# LMAT_AMT_V3.net
KiCad netlist of a schematic drawn in Altium Designer
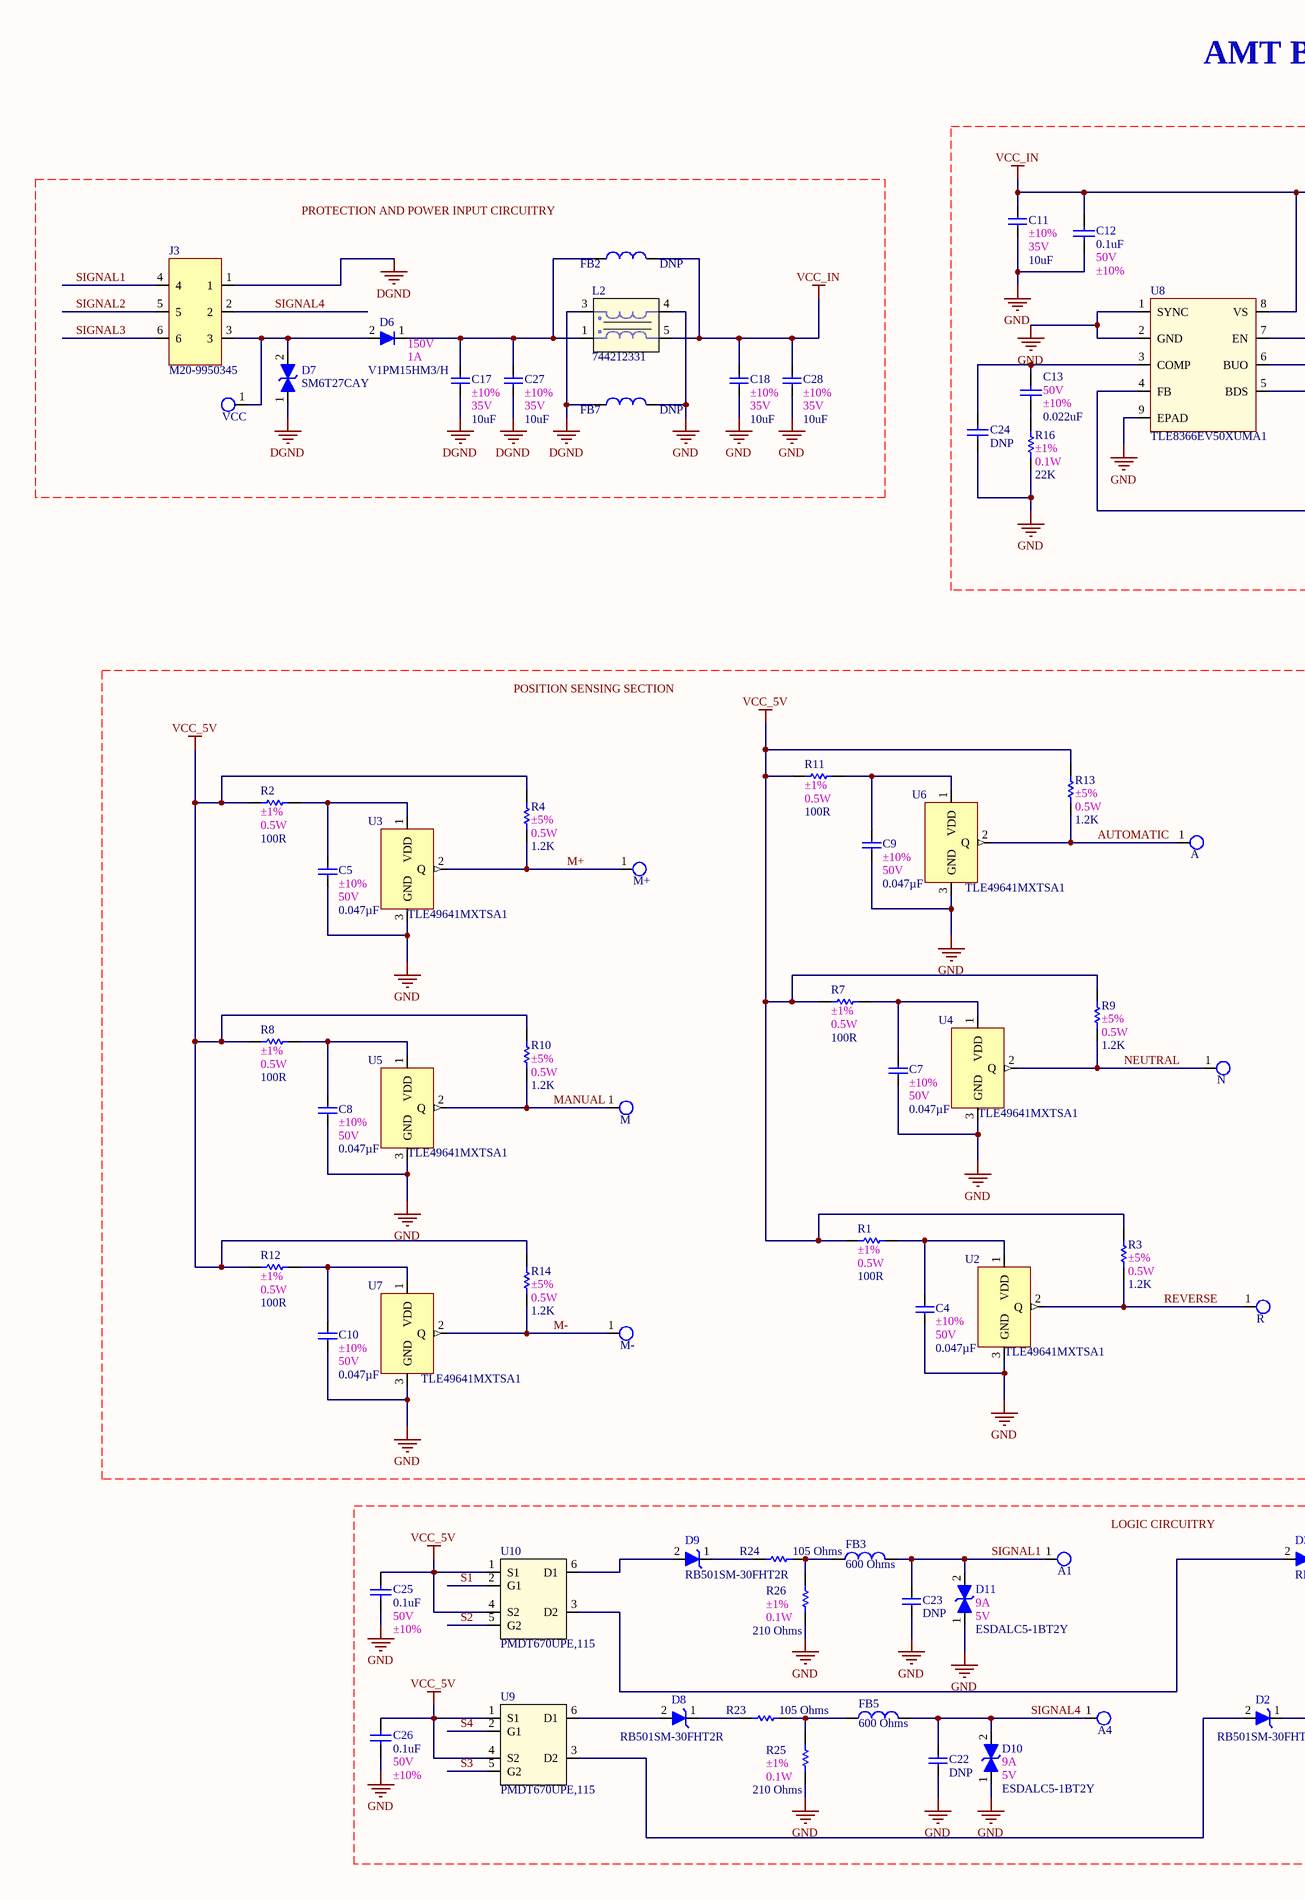
[diagram p0: LMAT_AMT_V3.SchDoc, left]
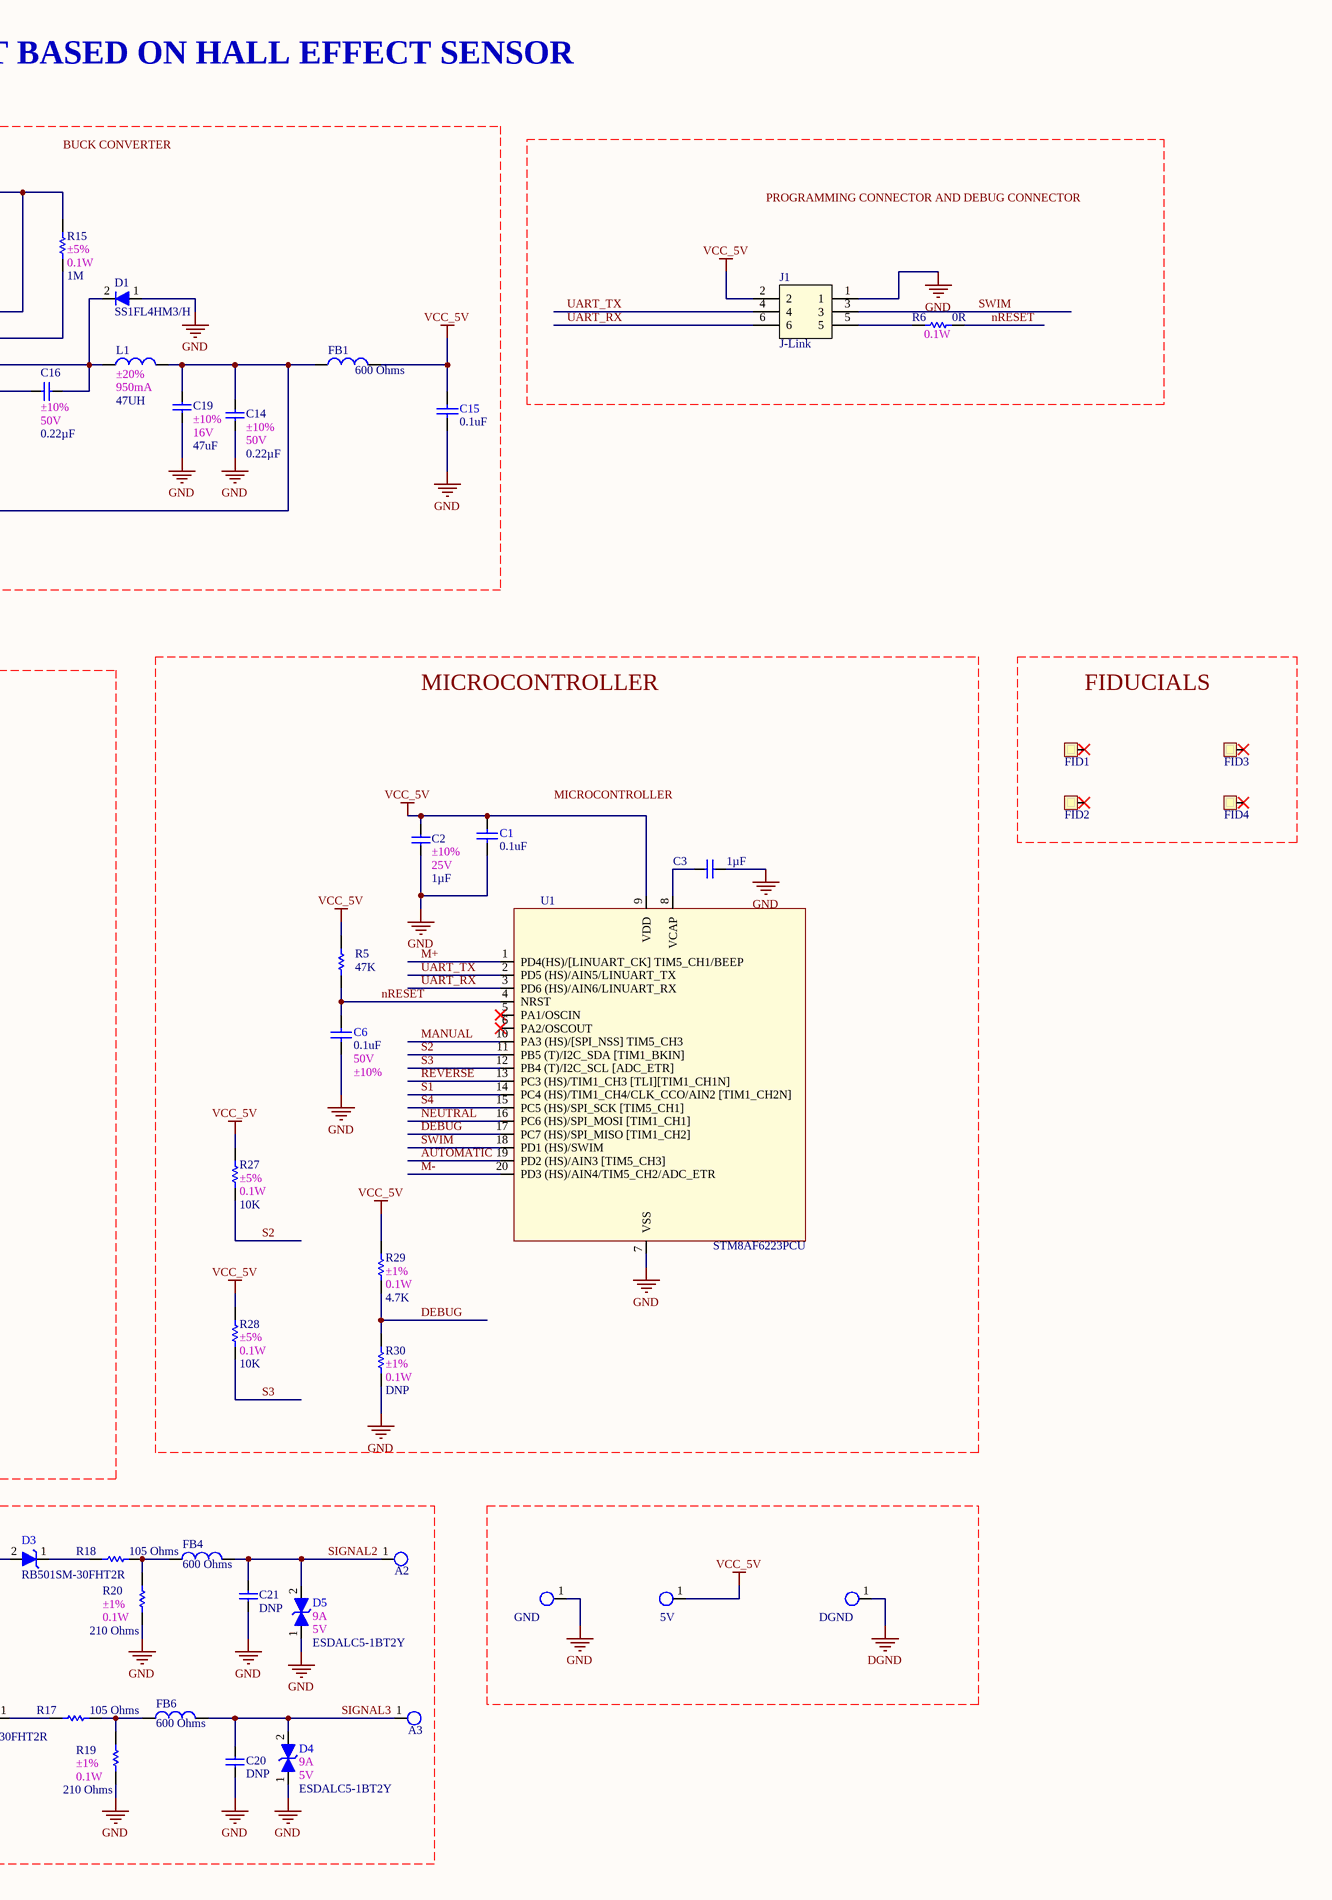
[diagram p1: LMAT_AMT_V3.SchDoc, right]

(export (version "E")
  (design (tool "Eeschema 10.0.6"))
  (components
    (comp (ref "5V")
      (value "Test Point- 35mil")
      (footprint "Master_Library:TP_35M_DIA")
      (fields (field (name "INTERNAL PART NUMBER") "EMS-TP35MIL-S"))
      (libsource (lib "Integrated_Master_Library") (part "EMS-TP35MIL-S"))
    )
    (comp (ref "A")
      (value "Test Point- 35mil")
      (footprint "Master_Library:TP_35M_DIA")
      (fields (field (name "INTERNAL PART NUMBER") "EMS-TP35MIL-S"))
      (libsource (lib "Integrated_Master_Library") (part "EMS-TP35MIL-S"))
    )
    (comp (ref "A1")
      (value "Test Point- 35mil")
      (footprint "Master_Library:TP_35M_DIA")
      (fields (field (name "INTERNAL PART NUMBER") "EMS-TP35MIL-S"))
      (libsource (lib "Integrated_Master_Library") (part "EMS-TP35MIL-S"))
    )
    (comp (ref "A2")
      (value "Test Point- 35mil")
      (footprint "Master_Library:TP_35M_DIA")
      (fields (field (name "INTERNAL PART NUMBER") "EMS-TP35MIL-S"))
      (libsource (lib "Integrated_Master_Library") (part "EMS-TP35MIL-S"))
    )
    (comp (ref "A3")
      (value "Test Point- 35mil")
      (footprint "Master_Library:TP_35M_DIA")
      (fields (field (name "INTERNAL PART NUMBER") "EMS-TP35MIL-S"))
      (libsource (lib "Integrated_Master_Library") (part "EMS-TP35MIL-S"))
    )
    (comp (ref "A4")
      (value "Test Point- 35mil")
      (footprint "Master_Library:TP_35M_DIA")
      (fields (field (name "INTERNAL PART NUMBER") "EMS-TP35MIL-S"))
      (libsource (lib "Integrated_Master_Library") (part "EMS-TP35MIL-S"))
    )
    (comp (ref "C1")
      (value "0.1uF")
      (footprint "Masterlib_auto:SMDC0603")
      (description "CAP CER 0.1UF 50V 10% X7R 0603")
      (fields
        (field (name "MANUFACTURER PART NUMBER") "CGA3E2X7R1H104K080AA")
        (field (name "MANUFACTURER") "TDK Corporation")
      )
      (libsource (lib "Integrated_Master_Library") (part "ECA0U10K50V0-SC"))
    )
    (comp (ref "C2")
      (value "1µF")
      (footprint "Masterlib_auto:SMDC0603")
      (description "CAP CER 1UF 25V X7R 0603")
      (fields
        (field (name "MANUFACTURER") "TDK Corporation")
        (field (name "VENDOR PART NUMBER") "445-173628-1-ND")
        (field (name "2ND AUXILIARY FIELD") "±10%")
        (field (name "1ST AUXILIARY FIELD") "25V")
      )
      (libsource (lib "Integrated_Master_Library (3)") (part "ECA1U00L25V0-SC"))
    )
    (comp (ref "C3")
      (value "1µF")
      (footprint "Masterlib_auto:SMDC0603")
      (description "CAP CER 1UF 25V X7R 0603")
      (fields
        (field (name "MANUFACTURER") "TDK Corporation")
        (field (name "VENDOR PART NUMBER") "445-173628-1-ND")
      )
      (libsource (lib "Integrated_Master_Library (3)") (part "ECA1U00L25V0-SC"))
    )
    (comp (ref "C4")
      (value "0.047µF")
      (footprint "Masterlib_auto:SMDC0603")
      (description "CAP CER 0.047UF 50V X7R 0603")
      (fields
        (field (name "MANUFACTURER") "TDK Corporation")
        (field (name "VENDOR PART NUMBER") "445-5664-1-ND")
        (field (name "2ND AUXILIARY FIELD") "±10%")
        (field (name "1ST AUXILIARY FIELD") "50V")
      )
      (libsource (lib "Integrated_Master_Library") (part "ECA47N0L50V-SC"))
    )
    (comp (ref "C5")
      (value "0.047µF")
      (footprint "Masterlib_auto:SMDC0603")
      (description "CAP CER 0.047UF 50V X7R 0603")
      (fields
        (field (name "MANUFACTURER") "TDK Corporation")
        (field (name "VENDOR PART NUMBER") "445-5664-1-ND")
        (field (name "2ND AUXILIARY FIELD") "±10%")
        (field (name "1ST AUXILIARY FIELD") "50V")
      )
      (libsource (lib "Integrated_Master_Library") (part "ECA47N0L50V-SC"))
    )
    (comp (ref "C6")
      (value "0.1uF")
      (footprint "Masterlib_auto:SMDC0603")
      (description "CAP CER 0.1UF 50V 10% X7R 0603")
      (fields
        (field (name "MANUFACTURER PART NUMBER") "CGA3E2X7R1H104K080AA")
        (field (name "MANUFACTURER") "TDK Corporation")
        (field (name "1ST AUXILIARY FIELD") "50V")
        (field (name "2ND AUXILIARY FIELD") "±10%")
      )
      (libsource (lib "Integrated_Master_Library") (part "ECA0U10K50V0-SC"))
    )
    (comp (ref "C7")
      (value "0.047µF")
      (footprint "Masterlib_auto:SMDC0603")
      (description "CAP CER 0.047UF 50V X7R 0603")
      (fields
        (field (name "MANUFACTURER") "TDK Corporation")
        (field (name "VENDOR PART NUMBER") "445-5664-1-ND")
        (field (name "2ND AUXILIARY FIELD") "±10%")
        (field (name "1ST AUXILIARY FIELD") "50V")
      )
      (libsource (lib "Integrated_Master_Library") (part "ECA47N0L50V-SC"))
    )
    (comp (ref "C8")
      (value "0.047µF")
      (footprint "Masterlib_auto:SMDC0603")
      (description "CAP CER 0.047UF 50V X7R 0603")
      (fields
        (field (name "MANUFACTURER") "TDK Corporation")
        (field (name "VENDOR PART NUMBER") "445-5664-1-ND")
        (field (name "2ND AUXILIARY FIELD") "±10%")
        (field (name "1ST AUXILIARY FIELD") "50V")
      )
      (libsource (lib "Integrated_Master_Library") (part "ECA47N0L50V-SC"))
    )
    (comp (ref "C9")
      (value "0.047µF")
      (footprint "Masterlib_auto:SMDC0603")
      (description "CAP CER 0.047UF 50V X7R 0603")
      (fields
        (field (name "MANUFACTURER") "TDK Corporation")
        (field (name "VENDOR PART NUMBER") "445-5664-1-ND")
        (field (name "2ND AUXILIARY FIELD") "±10%")
        (field (name "1ST AUXILIARY FIELD") "50V")
      )
      (libsource (lib "Integrated_Master_Library") (part "ECA47N0L50V-SC"))
    )
    (comp (ref "C10")
      (value "0.047µF")
      (footprint "Masterlib_auto:SMDC0603")
      (description "CAP CER 0.047UF 50V X7R 0603")
      (fields
        (field (name "MANUFACTURER") "TDK Corporation")
        (field (name "VENDOR PART NUMBER") "445-5664-1-ND")
        (field (name "2ND AUXILIARY FIELD") "±10%")
        (field (name "1ST AUXILIARY FIELD") "50V")
      )
      (libsource (lib "Integrated_Master_Library") (part "ECA47N0L50V-SC"))
    )
    (comp (ref "C11")
      (value "10uF")
      (footprint "Master_Library:SMDC1206")
      (description "CAP CER 10UF 35V X7R 1206")
      (fields
        (field (name "MANUFACTURER") "TDK Corporation")
        (field (name "VENDOR PART NUMBER") "445-174428-1-ND")
        (field (name "2ND AUXILIARY FIELD") "±10%")
        (field (name "1ST AUXILIARY FIELD") "35V")
      )
      (libsource (lib "Master_ Library") (part "ECA10U0L35V0-SG"))
    )
    (comp (ref "C12")
      (value "0.1uF")
      (footprint "Masterlib_auto:SMDC0603")
      (description "CAP CER 0.1UF 50V 10% X7R 0603")
      (fields
        (field (name "MANUFACTURER PART NUMBER") "CGA3E2X7R1H104K080AA")
        (field (name "MANUFACTURER") "TDK Corporation")
        (field (name "1ST AUXILIARY FIELD") "50V")
        (field (name "2ND AUXILIARY FIELD") "±10%")
      )
      (libsource (lib "Integrated_Master_Library") (part "ECA0U10K50V0-SC"))
    )
    (comp (ref "C13")
      (value "0.022uF")
      (footprint "Masterlib_auto:SMDC0603")
      (description "CAP CER 0.022UF 50V 10% X7R 0603")
      (fields
        (field (name "MANUFACTURER PART NUMBER") "CGA3E2X7R1H223K080AA")
        (field (name "MANUFACTURER") "TDK Corporation")
        (field (name "1ST AUXILIARY FIELD") "50V")
        (field (name "2ND AUXILIARY FIELD") "±10%")
      )
      (libsource (lib "Integrated_Master_Library") (part "ECA0U022K50V0-SC"))
    )
    (comp (ref "C14")
      (value "0.22µF")
      (footprint "Masterlib_auto:SMDC0603")
      (description "CAP CER 0.22UF 50V X7R 0603")
      (fields
        (field (name "MANUFACTURER") "Murata Electronics North America")
        (field (name "VENDOR PART NUMBER") "490-14410-1-ND")
        (field (name "2ND AUXILIARY FIELD") "±10%")
        (field (name "1ST AUXILIARY FIELD") "50V")
      )
      (libsource (lib "Integrated_Master_Library (3)") (part "ECA0U22L50V0-SC"))
    )
    (comp (ref "C15")
      (value "0.1uF")
      (footprint "Masterlib_auto:SMDC0603")
      (description "CAP CER 0.1UF 50V 10% X7R 0603")
      (fields
        (field (name "MANUFACTURER PART NUMBER") "CGA3E2X7R1H104K080AA")
        (field (name "MANUFACTURER") "TDK Corporation")
      )
      (libsource (lib "Integrated_Master_Library") (part "ECA0U10K50V0-SC"))
    )
    (comp (ref "C16")
      (value "0.22µF")
      (footprint "Masterlib_auto:SMDC0603")
      (description "CAP CER 0.22UF 50V X7R 0603")
      (fields
        (field (name "MANUFACTURER") "Murata Electronics North America")
        (field (name "VENDOR PART NUMBER") "490-14410-1-ND")
        (field (name "2ND AUXILIARY FIELD") "±10%")
        (field (name "1ST AUXILIARY FIELD") "50V")
      )
      (libsource (lib "Integrated_Master_Library") (part "ECA0U22L50V0-SC"))
    )
    (comp (ref "C17")
      (value "10uF")
      (footprint "Master_Library:SMDC1206")
      (description "CAP CER 10UF 35V X7R 1206")
      (fields
        (field (name "MANUFACTURER") "TDK Corporation")
        (field (name "VENDOR PART NUMBER") "445-174428-1-ND")
        (field (name "2ND AUXILIARY FIELD") "±10%")
        (field (name "1ST AUXILIARY FIELD") "35V")
      )
      (libsource (lib "Master_ Library") (part "ECA10U0L35V0-SG"))
    )
    (comp (ref "C18")
      (value "10uF")
      (footprint "Master_Library:SMDC1206")
      (description "CAP CER 10UF 35V X7R 1206")
      (fields
        (field (name "MANUFACTURER") "TDK Corporation")
        (field (name "VENDOR PART NUMBER") "445-174428-1-ND")
        (field (name "2ND AUXILIARY FIELD") "±10%")
        (field (name "1ST AUXILIARY FIELD") "35V")
      )
      (libsource (lib "Master_ Library") (part "ECA10U0L35V0-SG"))
    )
    (comp (ref "C19")
      (value "47uF")
      (footprint "Master_Library:SMDC1210")
      (description "CAP CER 47UF 16V X6S 1210")
      (fields
        (field (name "MANUFACTURER") "Murata Electronics North America")
        (field (name "VENDOR PART NUMBER") "490-12494-1-ND")
        (field (name "2ND AUXILIARY FIELD") "±10%")
        (field (name "1ST AUXILIARY FIELD") "16V")
      )
      (libsource (lib "Automobile-ML") (part "ECA47U0L16V0-SH"))
    )
    (comp (ref "C20")
      (value "DNP")
      (footprint "Masterlib_auto:SMDC0603")
      (description "CAP CER 10000PF 50V X8R 0603")
      (fields
        (field (name "MANUFACTURER") "TDK Corporation")
        (field (name "VENDOR PART NUMBER") "445-5892-1-ND")
      )
      (libsource (lib "Automobile-ML") (part "ECA0U01L50V0-SC"))
    )
    (comp (ref "C21")
      (value "DNP")
      (footprint "Masterlib_auto:SMDC0603")
      (description "CAP CER 10000PF 50V X8R 0603")
      (fields
        (field (name "MANUFACTURER") "TDK Corporation")
        (field (name "VENDOR PART NUMBER") "445-5892-1-ND")
      )
      (libsource (lib "Automobile-ML") (part "ECA0U01L50V0-SC"))
    )
    (comp (ref "C22")
      (value "DNP")
      (footprint "Masterlib_auto:SMDC0603")
      (description "CAP CER 10000PF 50V X8R 0603")
      (fields
        (field (name "MANUFACTURER") "TDK Corporation")
        (field (name "VENDOR PART NUMBER") "445-5892-1-ND")
      )
      (libsource (lib "Automobile-ML") (part "ECA0U01L50V0-SC"))
    )
    (comp (ref "C23")
      (value "DNP")
      (footprint "Masterlib_auto:SMDC0603")
      (description "CAP CER 10000PF 50V X8R 0603")
      (fields
        (field (name "MANUFACTURER") "TDK Corporation")
        (field (name "VENDOR PART NUMBER") "445-5892-1-ND")
      )
      (libsource (lib "Automobile-ML") (part "ECA0U01L50V0-SC"))
    )
    (comp (ref "C24")
      (value "DNP")
      (footprint "Masterlib_auto:SMDC0603")
      (description "CAP CER 0.022UF 50V 10% X7R 0603")
      (fields
        (field (name "MANUFACTURER PART NUMBER") "CGA3E2X7R1H223K080AA")
        (field (name "MANUFACTURER") "TDK Corporation")
      )
      (libsource (lib "Integrated_Master_Library") (part "ECA0U022K50V0-SC"))
    )
    (comp (ref "C25")
      (value "0.1uF")
      (footprint "Masterlib_auto:SMDC0603")
      (description "CAP CER 0.1UF 50V 10% X7R 0603")
      (fields
        (field (name "MANUFACTURER PART NUMBER") "CGA3E2X7R1H104K080AA")
        (field (name "MANUFACTURER") "TDK Corporation")
        (field (name "1ST AUXILIARY FIELD") "50V")
        (field (name "2ND AUXILIARY FIELD") "±10%")
      )
      (libsource (lib "Integrated_Master_Library") (part "ECA0U10K50V0-SC"))
    )
    (comp (ref "C26")
      (value "0.1uF")
      (footprint "Masterlib_auto:SMDC0603")
      (description "CAP CER 0.1UF 50V 10% X7R 0603")
      (fields
        (field (name "MANUFACTURER PART NUMBER") "CGA3E2X7R1H104K080AA")
        (field (name "MANUFACTURER") "TDK Corporation")
        (field (name "1ST AUXILIARY FIELD") "50V")
        (field (name "2ND AUXILIARY FIELD") "±10%")
      )
      (libsource (lib "Integrated_Master_Library") (part "ECA0U10K50V0-SC"))
    )
    (comp (ref "C27")
      (value "10uF")
      (footprint "Master_Library:SMDC1206")
      (description "CAP CER 10UF 35V X7R 1206")
      (fields
        (field (name "MANUFACTURER") "TDK Corporation")
        (field (name "VENDOR PART NUMBER") "445-174428-1-ND")
        (field (name "2ND AUXILIARY FIELD") "±10%")
        (field (name "1ST AUXILIARY FIELD") "35V")
      )
      (libsource (lib "Master_ Library") (part "ECA10U0L35V0-SG"))
    )
    (comp (ref "C28")
      (value "10uF")
      (footprint "Master_Library:SMDC1206")
      (description "CAP CER 10UF 35V X7R 1206")
      (fields
        (field (name "MANUFACTURER") "TDK Corporation")
        (field (name "VENDOR PART NUMBER") "445-174428-1-ND")
        (field (name "2ND AUXILIARY FIELD") "±10%")
        (field (name "1ST AUXILIARY FIELD") "35V")
      )
      (libsource (lib "Master_ Library") (part "ECA10U0L35V0-SG"))
    )
    (comp (ref "D1")
      (value "SS1FL4HM3/H")
      (footprint "Masterlib_auto:SODFL370X110-2N")
      (description "DIODE SCHOTTKY 40V 1A DO-219AB")
      (fields
        (field (name "MANUFACTURER") "Vishay Semiconductor Diodes Division")
        (field (name "INTERNAL PART NUMBER") "EDDVS1A0040V0-S")
      )
      (libsource (lib "Integrated_Master_Library (3)") (part "EDDVS1A0040V0-S"))
    )
    (comp (ref "D2")
      (value "RB501SM-30FHT2R")
      (footprint "Masterlib_auto:SOD1700X70N-V2")
      (description "Diode Schottky 30V 100mA Surface Mount EMD2")
      (fields
        (field (name "MANUFACTURER") "Rohm Semiconductor")
        (field (name "INTERNAL PART NUMBER") "EDDR0A1030V0-S")
      )
      (libsource (lib "Integrated_Master_Library (3)") (part "EDDR0A1030V0-S"))
    )
    (comp (ref "D3")
      (value "RB501SM-30FHT2R")
      (footprint "Masterlib_auto:SOD1700X70N-V2")
      (description "Diode Schottky 30V 100mA Surface Mount EMD2")
      (fields
        (field (name "MANUFACTURER") "Rohm Semiconductor")
        (field (name "INTERNAL PART NUMBER") "EDDR0A1030V0-S")
      )
      (libsource (lib "Integrated_Master_Library (3)") (part "EDDR0A1030V0-S"))
    )
    (comp (ref "D4")
      (value "ESDALC5-1BT2Y")
      (footprint "Master_Library:SOD1510X40")
      (description "TVS DIODE 5V 17.5V SOD882T")
      (fields
        (field (name "MANUFACTURER") "STMicroelectronics")
        (field (name "INTERNAL PART NUMBER") "EDDST9A005V00-S")
        (field (name "2ND AUXILIARY FIELD") "9A")
        (field (name "1ST AUXILIARY FIELD") "5V")
      )
      (libsource (lib "Master_ Library") (part "EDDST9A005V00-S"))
    )
    (comp (ref "D5")
      (value "ESDALC5-1BT2Y")
      (footprint "Master_Library:SOD1510X40")
      (description "TVS DIODE 5V 17.5V SOD882T")
      (fields
        (field (name "MANUFACTURER") "STMicroelectronics")
        (field (name "INTERNAL PART NUMBER") "EDDST9A005V00-S")
        (field (name "2ND AUXILIARY FIELD") "9A")
        (field (name "1ST AUXILIARY FIELD") "5V")
      )
      (libsource (lib "Master_ Library") (part "EDDST9A005V00-S"))
    )
    (comp (ref "D6")
      (value "V1PM15HM3/H")
      (footprint "MICROSMP (DO-219AD)")
      (description "DIODE SCHOTTKY 150V 1A MICROSMP")
      (fields
        (field (name "MANUFACTURER") "Vishay Semiconductor Diodes Division")
        (field (name "INTERNAL PART NUMBER") "EDDVS1A00150V-S")
        (field (name "1ST AUXILIARY FIELD") "150V")
        (field (name "2ND AUXILIARY FIELD") "1A")
      )
      (libsource (lib "Master_ Library") (part "EDDVS1A00150V-S"))
    )
    (comp (ref "D7")
      (value "SM6T27CAY")
      (footprint "Masterlib_auto:DIOM4336X26B")
      (description "TVS DIODE 23.1V 48.3V SMB")
      (fields
        (field (name "MANUFACTURER") "STMicroelectronics")
        (field (name "INTERNAL PART NUMBER") "EDDST83A025V7-S")
      )
      (libsource (lib "Integrated_Master_Library") (part "EDDST83A025V7-S"))
    )
    (comp (ref "D8")
      (value "RB501SM-30FHT2R")
      (footprint "Masterlib_auto:SOD1700X70N-V2")
      (description "Diode Schottky 30V 100mA Surface Mount EMD2")
      (fields
        (field (name "MANUFACTURER") "Rohm Semiconductor")
        (field (name "INTERNAL PART NUMBER") "EDDR0A1030V0-S")
      )
      (libsource (lib "Integrated_Master_Library (3)") (part "EDDR0A1030V0-S"))
    )
    (comp (ref "D9")
      (value "RB501SM-30FHT2R")
      (footprint "Masterlib_auto:SOD1700X70N-V2")
      (description "Diode Schottky 30V 100mA Surface Mount EMD2")
      (fields
        (field (name "MANUFACTURER") "Rohm Semiconductor")
        (field (name "INTERNAL PART NUMBER") "EDDR0A1030V0-S")
      )
      (libsource (lib "Integrated_Master_Library (3)") (part "EDDR0A1030V0-S"))
    )
    (comp (ref "D10")
      (value "ESDALC5-1BT2Y")
      (footprint "Master_Library:SOD1510X40")
      (description "TVS DIODE 5V 17.5V SOD882T")
      (fields
        (field (name "MANUFACTURER") "STMicroelectronics")
        (field (name "INTERNAL PART NUMBER") "EDDST9A005V00-S")
        (field (name "2ND AUXILIARY FIELD") "9A")
        (field (name "1ST AUXILIARY FIELD") "5V")
      )
      (libsource (lib "Master_ Library") (part "EDDST9A005V00-S"))
    )
    (comp (ref "D11")
      (value "ESDALC5-1BT2Y")
      (footprint "Master_Library:SOD1510X40")
      (description "TVS DIODE 5V 17.5V SOD882T")
      (fields
        (field (name "MANUFACTURER") "STMicroelectronics")
        (field (name "INTERNAL PART NUMBER") "EDDST9A005V00-S")
        (field (name "2ND AUXILIARY FIELD") "9A")
        (field (name "1ST AUXILIARY FIELD") "5V")
      )
      (libsource (lib "Master_ Library") (part "EDDST9A005V00-S"))
    )
    (comp (ref "DGND")
      (value "Test Point- 35mil")
      (footprint "Master_Library:TP_35M_DIA")
      (fields (field (name "INTERNAL PART NUMBER") "EMS-TP35MIL-S"))
      (libsource (lib "Integrated_Master_Library") (part "EMS-TP35MIL-S"))
    )
    (comp (ref "FB1")
      (value "600 Ohms")
      (footprint "SMDL0603")
      (description "FERRITE BEAD 600 OHM 0603 1LN")
      (fields
        (field (name "MANUFACTURER") "Würth Elektronik")
        (field (name "INTERNAL PART NUMBER") "EIN600R1A00-SC")
      )
      (libsource (lib "Master_ Library") (part "EIN600R1A00-SC"))
    )
    (comp (ref "FB2")
      (value "DNP")
      (footprint "SMDL0603")
      (description "FERRITE BEAD 600 OHM 0603 1LN")
      (fields
        (field (name "MANUFACTURER") "Würth Elektronik")
        (field (name "INTERNAL PART NUMBER") "EIN600R1A00-SC")
      )
      (libsource (lib "Master_ Library") (part "EIN600R1A00-SC"))
    )
    (comp (ref "FB3")
      (value "600 Ohms")
      (footprint "SMDL0603")
      (description "FERRITE BEAD 600 OHM 0603 1LN")
      (fields
        (field (name "MANUFACTURER") "Würth Elektronik")
        (field (name "INTERNAL PART NUMBER") "EIN600R1A00-SC")
      )
      (libsource (lib "Master_ Library") (part "EIN600R1A00-SC"))
    )
    (comp (ref "FB4")
      (value "600 Ohms")
      (footprint "SMDL0603")
      (description "FERRITE BEAD 600 OHM 0603 1LN")
      (fields
        (field (name "MANUFACTURER") "Würth Elektronik")
        (field (name "INTERNAL PART NUMBER") "EIN600R1A00-SC")
      )
      (libsource (lib "Master_ Library") (part "EIN600R1A00-SC"))
    )
    (comp (ref "FB5")
      (value "600 Ohms")
      (footprint "SMDL0603")
      (description "FERRITE BEAD 600 OHM 0603 1LN")
      (fields
        (field (name "MANUFACTURER") "Würth Elektronik")
        (field (name "INTERNAL PART NUMBER") "EIN600R1A00-SC")
      )
      (libsource (lib "Master_ Library") (part "EIN600R1A00-SC"))
    )
    (comp (ref "FB6")
      (value "600 Ohms")
      (footprint "SMDL0603")
      (description "FERRITE BEAD 600 OHM 0603 1LN")
      (fields
        (field (name "MANUFACTURER") "Würth Elektronik")
        (field (name "INTERNAL PART NUMBER") "EIN600R1A00-SC")
      )
      (libsource (lib "Master_ Library") (part "EIN600R1A00-SC"))
    )
    (comp (ref "FB7")
      (value "DNP")
      (footprint "SMDL0603")
      (description "FERRITE BEAD 600 OHM 0603 1LN")
      (fields
        (field (name "MANUFACTURER") "Würth Elektronik")
        (field (name "INTERNAL PART NUMBER") "EIN600R1A00-SC")
      )
      (libsource (lib "Master_ Library") (part "EIN600R1A00-SC"))
    )
    (comp (ref "FID1")
      (value "FID40X40")
      (footprint "Master_Library:FID40X40")
      (libsource (lib "Master_ Library") (part "FID_40X40"))
    )
    (comp (ref "FID2")
      (value "FID40X40")
      (footprint "Master_Library:FID40X40")
      (libsource (lib "Master_ Library") (part "FID_40X40"))
    )
    (comp (ref "FID3")
      (value "FID40X40")
      (footprint "Master_Library:FID40X40")
      (libsource (lib "Master_ Library") (part "FID_40X40"))
    )
    (comp (ref "FID4")
      (value "FID40X40")
      (footprint "Master_Library:FID40X40")
      (libsource (lib "Master_ Library") (part "FID_40X40"))
    )
    (comp (ref "GND")
      (value "Test Point- 35mil")
      (footprint "Master_Library:TP_35M_DIA")
      (fields (field (name "INTERNAL PART NUMBER") "EMS-TP35MIL-S"))
      (libsource (lib "Integrated_Master_Library") (part "EMS-TP35MIL-S"))
    )
    (comp (ref "J1")
      (value "J-LINK 6-PIN NEEDLE ADAPTER")
      (footprint "PRG_8.06.16 J-LINK 6-PIN NEEDLE ADAPTER")
      (fields
        (field (name "INTERNAL PART NUMBER") "EMS-8.06.16 J-LINK 6-PIN NEEDLE ADAPTER")
        (field (name "MANUFACTURER") "Segger Microcontroller Systems")
        (field (name "VENDOR PART NUMBER") "899-1051-ND")
        (field (name "1ST AUXILIARY FIELD") "J-Link")
      )
      (libsource (lib "Integrated_Master_Library") (part "EMS-8.06.16 J-LINK 6-PIN NEEDLE ADAPTER"))
    )
    (comp (ref "J3")
      (value "CONN HEADER R/A 6POS 2.54MM")
      (footprint "Masterlib_auto:HDRRA6W86P254_2X3_1344X254X528P_Modified")
      (fields
        (field (name "MANUFACTURER") "Harwin Inc.")
        (field (name "INTERNAL PART NUMBER") "ECN-M20-9950345-0003-0060")
        (field (name "VENDOR PART NUMBER") "952-2092-ND")
        (field (name "MANUFACTURER PART NUMBER") "M20-9950345")
      )
      (libsource (lib "Automobile-ML") (part "ECN-M20-9950345-0003-0060"))
    )
    (comp (ref "L1")
      (value "47UH")
      (footprint "Master_Library:INDC4949X310N")
      (description "FIXED IND 47UH 700MA 422.5 MOHM")
      (fields
        (field (name "MANUFACTURER") "Taiyo Yuden")
        (field (name "VENDOR PART NUMBER") "587-3604-1-ND")
        (field (name "2ND AUXILIARY FIELD") "±20%")
        (field (name "1ST AUXILIARY FIELD") "950mA")
      )
      (libsource (lib "Automobile-ML") (part "EIN47U0N950M-S"))
    )
    (comp (ref "L2")
      (value "744212331")
      (footprint "Master_Library:EMS_744212331")
      (description "CMC 330UH 300MA 2LN 2 KOHM SMD")
      (fields
        (field (name "MANUFACTURER") "Würth Elektronik")
        (field (name "INTERNAL PART NUMBER") "EIN330U300M-S")
      )
      (libsource (lib "Master_ Library") (part "EIN330U300M-S"))
    )
    (comp (ref "M")
      (value "Test Point- 35mil")
      (footprint "Master_Library:TP_35M_DIA")
      (fields (field (name "INTERNAL PART NUMBER") "EMS-TP35MIL-S"))
      (libsource (lib "Integrated_Master_Library") (part "EMS-TP35MIL-S"))
    )
    (comp (ref "M+")
      (value "Test Point- 35mil")
      (footprint "Master_Library:TP_35M_DIA")
      (fields (field (name "INTERNAL PART NUMBER") "EMS-TP35MIL-S"))
      (libsource (lib "Integrated_Master_Library") (part "EMS-TP35MIL-S"))
    )
    (comp (ref "M-")
      (value "Test Point- 35mil")
      (footprint "Master_Library:TP_35M_DIA")
      (fields (field (name "INTERNAL PART NUMBER") "EMS-TP35MIL-S"))
      (libsource (lib "Integrated_Master_Library") (part "EMS-TP35MIL-S"))
    )
    (comp (ref "N")
      (value "Test Point- 35mil")
      (footprint "Master_Library:TP_35M_DIA")
      (fields (field (name "INTERNAL PART NUMBER") "EMS-TP35MIL-S"))
      (libsource (lib "Integrated_Master_Library") (part "EMS-TP35MIL-S"))
    )
    (comp (ref "R")
      (value "Test Point- 35mil")
      (footprint "Master_Library:TP_35M_DIA")
      (fields (field (name "INTERNAL PART NUMBER") "EMS-TP35MIL-S"))
      (libsource (lib "Integrated_Master_Library") (part "EMS-TP35MIL-S"))
    )
    (comp (ref "R1")
      (value "100R")
      (footprint "Masterlib_auto:SMDR0805")
      (description "RES SMD 100 OHM 1% 1/2W 0805")
      (fields
        (field (name "MANUFACTURER PART NUMBER") "ERJ-P06F1000V")
        (field (name "MANUFACTURER") "Panasonic Electronic Components")
        (field (name "2ND AUXILIARY FIELD") "±1%")
        (field (name "1ST AUXILIARY FIELD") "0.5W")
      )
      (libsource (lib "Automobile-ML") (part "ERE100RG120-SE"))
    )
    (comp (ref "R2")
      (value "100R")
      (footprint "Masterlib_auto:SMDR0805")
      (description "RES SMD 100 OHM 1% 1/2W 0805")
      (fields
        (field (name "MANUFACTURER PART NUMBER") "ERJ-P06F1000V")
        (field (name "MANUFACTURER") "Panasonic Electronic Components")
        (field (name "2ND AUXILIARY FIELD") "±1%")
        (field (name "1ST AUXILIARY FIELD") "0.5W")
      )
      (libsource (lib "Automobile-ML") (part "ERE100RG120-SE"))
    )
    (comp (ref "R3")
      (value "1.2K")
      (footprint "Masterlib_auto:SMDR0805")
      (description "RES SMD 1.2K OHM 5% 1/2W 0805")
      (fields
        (field (name "MANUFACTURER") "Panasonic Electronic Components")
        (field (name "VENDOR PART NUMBER") "P1.2KADCT-ND")
        (field (name "2ND AUXILIARY FIELD") "±5%")
        (field (name "1ST AUXILIARY FIELD") "0.5W")
      )
      (libsource (lib "Integrated_Master_Library") (part "ERE1K20G102-SE"))
    )
    (comp (ref "R4")
      (value "1.2K")
      (footprint "Masterlib_auto:SMDR0805")
      (description "RES SMD 1.2K OHM 5% 1/2W 0805")
      (fields
        (field (name "MANUFACTURER") "Panasonic Electronic Components")
        (field (name "VENDOR PART NUMBER") "P1.2KADCT-ND")
        (field (name "2ND AUXILIARY FIELD") "±5%")
        (field (name "1ST AUXILIARY FIELD") "0.5W")
      )
      (libsource (lib "Integrated_Master_Library") (part "ERE1K20G102-SE"))
    )
    (comp (ref "R5")
      (value "47K")
      (footprint "Masterlib_auto:SMDR0603")
      (description "RES SMD 47K OHM 1% 1/10W 0603")
      (fields (field (name "MANUFACTURER") "Yageo") (field (name "VENDOR PART NUMBER") "YAG2129CT-ND"))
      (libsource (lib "Integrated_Master_Library (3)") (part "ERE47K0G110-SC"))
    )
    (comp (ref "R6")
      (value "0R")
      (footprint "Masterlib_auto:SMDR0603")
      (description "RES SMD 0.0OHM JUMPER 1/10W 0603")
      (fields
        (field (name "MANUFACTURER PART NUMBER") "ERJ-3GEY0R00V")
        (field (name "MANUFACTURER") "Panasonic Electronic Components")
        (field (name "1ST AUXILIARY FIELD") "0.1W")
      )
      (libsource (lib "Integrated_Master_Library") (part "ERE0R00110-SC"))
    )
    (comp (ref "R7")
      (value "100R")
      (footprint "Masterlib_auto:SMDR0805")
      (description "RES SMD 100 OHM 1% 1/2W 0805")
      (fields
        (field (name "MANUFACTURER PART NUMBER") "ERJ-P06F1000V")
        (field (name "MANUFACTURER") "Panasonic Electronic Components")
        (field (name "2ND AUXILIARY FIELD") "±1%")
        (field (name "1ST AUXILIARY FIELD") "0.5W")
      )
      (libsource (lib "Automobile-ML") (part "ERE100RG120-SE"))
    )
    (comp (ref "R8")
      (value "100R")
      (footprint "Masterlib_auto:SMDR0805")
      (description "RES SMD 100 OHM 1% 1/2W 0805")
      (fields
        (field (name "MANUFACTURER PART NUMBER") "ERJ-P06F1000V")
        (field (name "MANUFACTURER") "Panasonic Electronic Components")
        (field (name "2ND AUXILIARY FIELD") "±1%")
        (field (name "1ST AUXILIARY FIELD") "0.5W")
      )
      (libsource (lib "Automobile-ML") (part "ERE100RG120-SE"))
    )
    (comp (ref "R9")
      (value "1.2K")
      (footprint "Masterlib_auto:SMDR0805")
      (description "RES SMD 1.2K OHM 5% 1/2W 0805")
      (fields
        (field (name "MANUFACTURER") "Panasonic Electronic Components")
        (field (name "VENDOR PART NUMBER") "P1.2KADCT-ND")
        (field (name "2ND AUXILIARY FIELD") "±5%")
        (field (name "1ST AUXILIARY FIELD") "0.5W")
      )
      (libsource (lib "Integrated_Master_Library") (part "ERE1K20G102-SE"))
    )
    (comp (ref "R10")
      (value "1.2K")
      (footprint "Masterlib_auto:SMDR0805")
      (description "RES SMD 1.2K OHM 5% 1/2W 0805")
      (fields
        (field (name "MANUFACTURER") "Panasonic Electronic Components")
        (field (name "VENDOR PART NUMBER") "P1.2KADCT-ND")
        (field (name "2ND AUXILIARY FIELD") "±5%")
        (field (name "1ST AUXILIARY FIELD") "0.5W")
      )
      (libsource (lib "Integrated_Master_Library") (part "ERE1K20G102-SE"))
    )
    (comp (ref "R11")
      (value "100R")
      (footprint "Masterlib_auto:SMDR0805")
      (description "RES SMD 100 OHM 1% 1/2W 0805")
      (fields
        (field (name "MANUFACTURER PART NUMBER") "ERJ-P06F1000V")
        (field (name "MANUFACTURER") "Panasonic Electronic Components")
        (field (name "2ND AUXILIARY FIELD") "±1%")
        (field (name "1ST AUXILIARY FIELD") "0.5W")
      )
      (libsource (lib "Automobile-ML") (part "ERE100RG120-SE"))
    )
    (comp (ref "R12")
      (value "100R")
      (footprint "Masterlib_auto:SMDR0805")
      (description "RES SMD 100 OHM 1% 1/2W 0805")
      (fields
        (field (name "MANUFACTURER PART NUMBER") "ERJ-P06F1000V")
        (field (name "MANUFACTURER") "Panasonic Electronic Components")
        (field (name "2ND AUXILIARY FIELD") "±1%")
        (field (name "1ST AUXILIARY FIELD") "0.5W")
      )
      (libsource (lib "Automobile-ML") (part "ERE100RG120-SE"))
    )
    (comp (ref "R13")
      (value "1.2K")
      (footprint "Masterlib_auto:SMDR0805")
      (description "RES SMD 1.2K OHM 5% 1/2W 0805")
      (fields
        (field (name "MANUFACTURER") "Panasonic Electronic Components")
        (field (name "VENDOR PART NUMBER") "P1.2KADCT-ND")
        (field (name "2ND AUXILIARY FIELD") "±5%")
        (field (name "1ST AUXILIARY FIELD") "0.5W")
      )
      (libsource (lib "Integrated_Master_Library") (part "ERE1K20G102-SE"))
    )
    (comp (ref "R14")
      (value "1.2K")
      (footprint "Masterlib_auto:SMDR0805")
      (description "RES SMD 1.2K OHM 5% 1/2W 0805")
      (fields
        (field (name "MANUFACTURER") "Panasonic Electronic Components")
        (field (name "VENDOR PART NUMBER") "P1.2KADCT-ND")
        (field (name "2ND AUXILIARY FIELD") "±5%")
        (field (name "1ST AUXILIARY FIELD") "0.5W")
      )
      (libsource (lib "Integrated_Master_Library") (part "ERE1K20G102-SE"))
    )
    (comp (ref "R15")
      (value "1M")
      (footprint "Masterlib_auto:SMDR0603")
      (description "RES SMD 1M OHM 5% 1/10W 0603")
      (fields
        (field (name "MANUFACTURER") "Vishay Dale")
        (field (name "VENDOR PART NUMBER") "541-2216-1-ND")
        (field (name "2ND AUXILIARY FIELD") "±5%")
        (field (name "1ST AUXILIARY FIELD") "0.1W")
      )
      (libsource (lib "Automobile-ML") (part "ERE1M00K110-SC"))
    )
    (comp (ref "R16")
      (value "22K")
      (footprint "Masterlib_auto:SMDR0603")
      (description "RES SMD 22K OHM 1% 1/10W 0603")
      (fields
        (field (name "MANUFACTURER") "Panasonic Electronic Components")
        (field (name "VENDOR PART NUMBER") "P22.0KHCT-ND")
        (field (name "2ND AUXILIARY FIELD") "±1%")
        (field (name "1ST AUXILIARY FIELD") "0.1W")
      )
      (libsource (lib "Automobile-ML") (part "ERE22K0G110-SC"))
    )
    (comp (ref "R17")
      (value "105 Ohms")
      (footprint "Masterlib_auto:SMDR0603")
      (description "RES SMD 105 OHM 1% 1/10W 0603")
      (fields
        (field (name "MANUFACTURER") "Panasonic Electronic Components")
        (field (name "VENDOR PART NUMBER") "P105HCT-ND")
      )
      (libsource (lib "Automobile-ML") (part "ERE105RG110-SC"))
    )
    (comp (ref "R18")
      (value "105 Ohms")
      (footprint "Masterlib_auto:SMDR0603")
      (description "RES SMD 105 OHM 1% 1/10W 0603")
      (fields
        (field (name "MANUFACTURER") "Panasonic Electronic Components")
        (field (name "VENDOR PART NUMBER") "P105HCT-ND")
      )
      (libsource (lib "Automobile-ML") (part "ERE105RG110-SC"))
    )
    (comp (ref "R19")
      (value "210 Ohms")
      (footprint "Masterlib_auto:SMDR0603")
      (description "RES SMD 210 OHM 1% 1/10W 0603")
      (fields
        (field (name "MANUFACTURER") "Panasonic Electronic Components")
        (field (name "VENDOR PART NUMBER") "P210HCT-ND")
        (field (name "2ND AUXILIARY FIELD") "±1%")
        (field (name "1ST AUXILIARY FIELD") "0.1W")
      )
      (libsource (lib "Automobile-ML") (part "ERE210RG110-SC"))
    )
    (comp (ref "R20")
      (value "210 Ohms")
      (footprint "Masterlib_auto:SMDR0603")
      (description "RES SMD 210 OHM 1% 1/10W 0603")
      (fields
        (field (name "MANUFACTURER") "Panasonic Electronic Components")
        (field (name "VENDOR PART NUMBER") "P210HCT-ND")
        (field (name "2ND AUXILIARY FIELD") "±1%")
        (field (name "1ST AUXILIARY FIELD") "0.1W")
      )
      (libsource (lib "Automobile-ML") (part "ERE210RG110-SC"))
    )
    (comp (ref "R23")
      (value "105 Ohms")
      (footprint "Masterlib_auto:SMDR0603")
      (description "RES SMD 105 OHM 1% 1/10W 0603")
      (fields
        (field (name "MANUFACTURER") "Panasonic Electronic Components")
        (field (name "VENDOR PART NUMBER") "P105HCT-ND")
      )
      (libsource (lib "Automobile-ML") (part "ERE105RG110-SC"))
    )
    (comp (ref "R24")
      (value "105 Ohms")
      (footprint "Masterlib_auto:SMDR0603")
      (description "RES SMD 105 OHM 1% 1/10W 0603")
      (fields
        (field (name "MANUFACTURER") "Panasonic Electronic Components")
        (field (name "VENDOR PART NUMBER") "P105HCT-ND")
      )
      (libsource (lib "Automobile-ML") (part "ERE105RG110-SC"))
    )
    (comp (ref "R25")
      (value "210 Ohms")
      (footprint "Masterlib_auto:SMDR0603")
      (description "RES SMD 210 OHM 1% 1/10W 0603")
      (fields
        (field (name "MANUFACTURER") "Panasonic Electronic Components")
        (field (name "VENDOR PART NUMBER") "P210HCT-ND")
        (field (name "2ND AUXILIARY FIELD") "±1%")
        (field (name "1ST AUXILIARY FIELD") "0.1W")
      )
      (libsource (lib "Automobile-ML") (part "ERE210RG110-SC"))
    )
    (comp (ref "R26")
      (value "210 Ohms")
      (footprint "Masterlib_auto:SMDR0603")
      (description "RES SMD 210 OHM 1% 1/10W 0603")
      (fields
        (field (name "MANUFACTURER") "Panasonic Electronic Components")
        (field (name "VENDOR PART NUMBER") "P210HCT-ND")
        (field (name "2ND AUXILIARY FIELD") "±1%")
        (field (name "1ST AUXILIARY FIELD") "0.1W")
      )
      (libsource (lib "Automobile-ML") (part "ERE210RG110-SC"))
    )
    (comp (ref "R27")
      (value "10K")
      (footprint "Masterlib_auto:SMDR0402")
      (description "RES SMD 10K OHM 5% 1/10W 0402")
      (fields
        (field (name "MANUFACTURER") "Panasonic Electronic Components")
        (field (name "VENDOR PART NUMBER") "P10KJCT-ND")
        (field (name "2ND AUXILIARY FIELD") "±5%")
        (field (name "1ST AUXILIARY FIELD") "0.1W")
      )
      (libsource (lib "Automobile-ML") (part "ERE10K0K110-SB"))
    )
    (comp (ref "R28")
      (value "10K")
      (footprint "Masterlib_auto:SMDR0402")
      (description "RES SMD 10K OHM 5% 1/10W 0402")
      (fields
        (field (name "MANUFACTURER") "Panasonic Electronic Components")
        (field (name "VENDOR PART NUMBER") "P10KJCT-ND")
        (field (name "2ND AUXILIARY FIELD") "±5%")
        (field (name "1ST AUXILIARY FIELD") "0.1W")
      )
      (libsource (lib "Automobile-ML") (part "ERE10K0K110-SB"))
    )
    (comp (ref "R29")
      (value "4.7K")
      (footprint "Masterlib_auto:SMDR0402")
      (description "RES SMD 4.7K OHM 1% 1/10W 0402")
      (fields
        (field (name "MANUFACTURER") "Panasonic Electronic Components")
        (field (name "VENDOR PART NUMBER") "P4.70KLCT-ND")
        (field (name "2ND AUXILIARY FIELD") "±1%")
        (field (name "1ST AUXILIARY FIELD") "0.1W")
      )
      (libsource (lib "Automobile-ML") (part "ERE4K70G110-SB"))
    )
    (comp (ref "R30")
      (value "DNP")
      (footprint "Masterlib_auto:SMDR0402")
      (description "RES SMD 4.7K OHM 1% 1/10W 0402")
      (fields
        (field (name "MANUFACTURER") "Panasonic Electronic Components")
        (field (name "VENDOR PART NUMBER") "P4.70KLCT-ND")
        (field (name "2ND AUXILIARY FIELD") "±1%")
        (field (name "1ST AUXILIARY FIELD") "0.1W")
      )
      (libsource (lib "Automobile-ML") (part "ERE4K70G110-SB"))
    )
    (comp (ref "U1")
      (value "STM8AF6223PCU")
      (footprint "Masterlib_auto:SOP65P640X120-20N")
      (description "IC MCU 8BIT 8KB FLASH 20TSSOP")
      (fields
        (field (name "MANUFACTURER") "STMicroelectronics")
        (field (name "INTERNAL PART NUMBER") "EICSTMTSSOP-20-1691")
      )
      (libsource (lib "Integrated_Master_Library (3)") (part "EICSTMTSSOP-20-1691"))
    )
    (comp (ref "U2")
      (value "TLE49641MXTSA1")
      (footprint "Master_Library:SOT95P248X115-3N")
      (description "MAGNETIC SWITCH UNIPOLAR SOT23-3")
      (fields
        (field (name "MANUFACTURER") "Infineon Technologies")
        (field (name "VENDOR PART NUMBER") "TLE49641MXTSA1CT-ND")
      )
      (libsource (lib "Integrated_Master_Library") (part "EICITSOT23-3-1528"))
    )
    (comp (ref "U3")
      (value "TLE49641MXTSA1")
      (footprint "Master_Library:SOT95P248X115-3N")
      (description "MAGNETIC SWITCH UNIPOLAR SOT23-3")
      (fields
        (field (name "MANUFACTURER") "Infineon Technologies")
        (field (name "VENDOR PART NUMBER") "TLE49641MXTSA1CT-ND")
      )
      (libsource (lib "Integrated_Master_Library") (part "EICITSOT23-3-1528"))
    )
    (comp (ref "U4")
      (value "TLE49641MXTSA1")
      (footprint "Master_Library:SOT95P248X115-3N")
      (description "MAGNETIC SWITCH UNIPOLAR SOT23-3")
      (fields
        (field (name "MANUFACTURER") "Infineon Technologies")
        (field (name "VENDOR PART NUMBER") "TLE49641MXTSA1CT-ND")
      )
      (libsource (lib "Integrated_Master_Library") (part "EICITSOT23-3-1528"))
    )
    (comp (ref "U5")
      (value "TLE49641MXTSA1")
      (footprint "Master_Library:SOT95P248X115-3N")
      (description "MAGNETIC SWITCH UNIPOLAR SOT23-3")
      (fields
        (field (name "MANUFACTURER") "Infineon Technologies")
        (field (name "VENDOR PART NUMBER") "TLE49641MXTSA1CT-ND")
      )
      (libsource (lib "Integrated_Master_Library") (part "EICITSOT23-3-1528"))
    )
    (comp (ref "U6")
      (value "TLE49641MXTSA1")
      (footprint "Master_Library:SOT95P248X115-3N")
      (description "MAGNETIC SWITCH UNIPOLAR SOT23-3")
      (fields
        (field (name "MANUFACTURER") "Infineon Technologies")
        (field (name "VENDOR PART NUMBER") "TLE49641MXTSA1CT-ND")
      )
      (libsource (lib "Integrated_Master_Library") (part "EICITSOT23-3-1528"))
    )
    (comp (ref "U7")
      (value "TLE49641MXTSA1")
      (footprint "Master_Library:SOT95P248X115-3N")
      (description "MAGNETIC SWITCH UNIPOLAR SOT23-3")
      (fields
        (field (name "MANUFACTURER") "Infineon Technologies")
        (field (name "VENDOR PART NUMBER") "TLE49641MXTSA1CT-ND")
      )
      (libsource (lib "Integrated_Master_Library") (part "EICITSOT23-3-1528"))
    )
    (comp (ref "U8")
      (value "TLE8366EV50XUMA1")
      (footprint "Masterlib_auto:SOIC127P600X170_HS-9N")
      (description "IC REG BUCK 5V 1.8A 8DSO")
      (fields
        (field (name "MANUFACTURER") "Infineon Technologies")
        (field (name "INTERNAL PART NUMBER") "EICITSOIC-08-0001")
      )
      (libsource (lib "Automobile-ML") (part "EICITSOIC-08-0001"))
    )
    (comp (ref "U9")
      (value "PMDT670UPE,115")
      (footprint "Masterlib_auto:SOTFL50P160X60-6N")
      (description "MOSFET 2P-CH 20V 0.55A SOT666")
      (fields
        (field (name "MANUFACTURER") "Nexperia USA Inc.")
        (field (name "INTERNAL PART NUMBER") "EICNUSOT666-06-0004")
      )
      (libsource (lib "Automobile-ML") (part "EICNUSOT666-06-0004"))
    )
    (comp (ref "U10")
      (value "PMDT670UPE,115")
      (footprint "Masterlib_auto:SOTFL50P160X60-6N")
      (description "MOSFET 2P-CH 20V 0.55A SOT666")
      (fields
        (field (name "MANUFACTURER") "Nexperia USA Inc.")
        (field (name "INTERNAL PART NUMBER") "EICNUSOT666-06-0004")
      )
      (libsource (lib "Automobile-ML") (part "EICNUSOT666-06-0004"))
    )
    (comp (ref "VCC")
      (value "Test Point- 35mil")
      (footprint "Master_Library:TP_35M_DIA")
      (fields (field (name "INTERNAL PART NUMBER") "EMS-TP35MIL-S"))
      (libsource (lib "Integrated_Master_Library") (part "EMS-TP35MIL-S"))
    )
  )
  (nets
    (net (code "1") (name "/AUTOMATIC") (class "Default")
      (node (ref "A") (pin "1") (pinfunction "1_1") (pintype "passive"))
      (node (ref "R13") (pin "2") (pinfunction "2_2") (pintype "passive"))
      (node (ref "U1") (pin "19") (pinfunction "PD2_(HS)/AIN3_[TIM5_CH3]_19") (pintype "passive"))
      (node (ref "U6") (pin "2") (pinfunction "Q_2") (pintype "output"))
    )
    (net (code "2") (name "/DEBUG") (class "Default")
      (node (ref "R29") (pin "1") (pinfunction "1_1") (pintype "passive"))
      (node (ref "R30") (pin "2") (pinfunction "2_2") (pintype "passive"))
      (node (ref "U1") (pin "17") (pinfunction "PC7_(HS)/SPI_MISO_[TIM1_CH2]_17") (pintype "passive"))
    )
    (net (code "3") (name "/M+") (class "Default")
      (node (ref "M+") (pin "1") (pinfunction "1_1") (pintype "passive"))
      (node (ref "R4") (pin "2") (pinfunction "2_2") (pintype "passive"))
      (node (ref "U1") (pin "1") (pinfunction "PD4(HS)/[LINUART_CK]_TIM5_CH1/BEEP_1") (pintype "passive"))
      (node (ref "U3") (pin "2") (pinfunction "Q_2") (pintype "output"))
    )
    (net (code "4") (name "/M-") (class "Default")
      (node (ref "M-") (pin "1") (pinfunction "1_1") (pintype "passive"))
      (node (ref "R14") (pin "2") (pinfunction "2_2") (pintype "passive"))
      (node (ref "U1") (pin "20") (pinfunction "PD3_(HS)/AIN4/TIM5_CH2/ADC_ETR_20") (pintype "passive"))
      (node (ref "U7") (pin "2") (pinfunction "Q_2") (pintype "output"))
    )
    (net (code "5") (name "/MANUAL") (class "Default")
      (node (ref "M") (pin "1") (pinfunction "1_1") (pintype "passive"))
      (node (ref "R10") (pin "2") (pinfunction "2_2") (pintype "passive"))
      (node (ref "U1") (pin "10") (pinfunction "PA3_(HS)/[SPI_NSS]_TIM5_CH3_10") (pintype "passive"))
      (node (ref "U5") (pin "2") (pinfunction "Q_2") (pintype "output"))
    )
    (net (code "6") (name "/NEUTRAL") (class "Default")
      (node (ref "N") (pin "1") (pinfunction "1_1") (pintype "passive"))
      (node (ref "R9") (pin "2") (pinfunction "2_2") (pintype "passive"))
      (node (ref "U1") (pin "16") (pinfunction "PC6_(HS)/SPI_MOSI_[TIM1_CH1]_16") (pintype "passive"))
      (node (ref "U4") (pin "2") (pinfunction "Q_2") (pintype "output"))
    )
    (net (code "7") (name "/REVERSE") (class "Default")
      (node (ref "R") (pin "1") (pinfunction "1_1") (pintype "passive"))
      (node (ref "R3") (pin "2") (pinfunction "2_2") (pintype "passive"))
      (node (ref "U1") (pin "13") (pinfunction "PC3_(HS)/TIM1_CH3_[TLI][TIM1_CH1N]_13") (pintype "passive"))
      (node (ref "U2") (pin "2") (pinfunction "Q_2") (pintype "output"))
    )
    (net (code "8") (name "/S1") (class "Default")
      (node (ref "U1") (pin "14") (pinfunction "PC4_(HS)/TIM1_CH4/CLK_CCO/AIN2_[TIM1_CH2N]_14") (pintype "passive"))
      (node (ref "U10") (pin "2") (pinfunction "G1_2") (pintype "passive"))
    )
    (net (code "9") (name "/S2") (class "Default")
      (node (ref "R27") (pin "1") (pinfunction "1_1") (pintype "passive"))
      (node (ref "U1") (pin "11") (pinfunction "PB5_(T)/I2C_SDA_[TIM1_BKIN]_11") (pintype "passive"))
      (node (ref "U10") (pin "5") (pinfunction "G2_5") (pintype "passive"))
    )
    (net (code "10") (name "/S3") (class "Default")
      (node (ref "R28") (pin "1") (pinfunction "1_1") (pintype "passive"))
      (node (ref "U1") (pin "12") (pinfunction "PB4_(T)/I2C_SCL_[ADC_ETR]_12") (pintype "passive"))
      (node (ref "U9") (pin "5") (pinfunction "G2_5") (pintype "passive"))
    )
    (net (code "11") (name "/S4") (class "Default")
      (node (ref "U1") (pin "15") (pinfunction "PC5_(HS)/SPI_SCK_[TIM5_CH1]_15") (pintype "passive"))
      (node (ref "U9") (pin "2") (pinfunction "G1_2") (pintype "passive"))
    )
    (net (code "12") (name "/SIGNAL1") (class "Default")
      (node (ref "A1") (pin "1") (pinfunction "1_1") (pintype "passive"))
      (node (ref "C23") (pin "2") (pinfunction "2_2") (pintype "passive"))
      (node (ref "D11") (pin "2") (pinfunction "2_2") (pintype "passive"))
      (node (ref "FB3") (pin "2") (pinfunction "2_2") (pintype "passive"))
      (node (ref "J3") (pin "4") (pinfunction "4_4") (pintype "passive"))
    )
    (net (code "13") (name "/SIGNAL2") (class "Default")
      (node (ref "A2") (pin "1") (pinfunction "1_1") (pintype "passive"))
      (node (ref "C21") (pin "2") (pinfunction "2_2") (pintype "passive"))
      (node (ref "D5") (pin "2") (pinfunction "2_2") (pintype "passive"))
      (node (ref "FB4") (pin "2") (pinfunction "2_2") (pintype "passive"))
      (node (ref "J3") (pin "5") (pinfunction "5_5") (pintype "passive"))
    )
    (net (code "14") (name "/SIGNAL3") (class "Default")
      (node (ref "A3") (pin "1") (pinfunction "1_1") (pintype "passive"))
      (node (ref "C20") (pin "2") (pinfunction "2_2") (pintype "passive"))
      (node (ref "D4") (pin "2") (pinfunction "2_2") (pintype "passive"))
      (node (ref "FB6") (pin "2") (pinfunction "2_2") (pintype "passive"))
      (node (ref "J3") (pin "6") (pinfunction "6_6") (pintype "passive"))
    )
    (net (code "15") (name "/SIGNAL4") (class "Default")
      (node (ref "A4") (pin "1") (pinfunction "1_1") (pintype "passive"))
      (node (ref "C22") (pin "2") (pinfunction "2_2") (pintype "passive"))
      (node (ref "D10") (pin "2") (pinfunction "2_2") (pintype "passive"))
      (node (ref "FB5") (pin "2") (pinfunction "2_2") (pintype "passive"))
      (node (ref "J3") (pin "2") (pinfunction "2_2") (pintype "passive"))
    )
    (net (code "16") (name "/SWIM") (class "Default")
      (node (ref "J1") (pin "3") (pinfunction "3_3") (pintype "passive"))
      (node (ref "U1") (pin "18") (pinfunction "PD1_(HS)/SWIM_18") (pintype "passive"))
    )
    (net (code "17") (name "/UART_RX") (class "Default")
      (node (ref "J1") (pin "6") (pinfunction "6_6") (pintype "passive"))
      (node (ref "U1") (pin "3") (pinfunction "PD6_(HS)/AIN6/LINUART_RX_3") (pintype "passive"))
    )
    (net (code "18") (name "/UART_TX") (class "Default")
      (node (ref "J1") (pin "4") (pinfunction "4_4") (pintype "passive"))
      (node (ref "U1") (pin "2") (pinfunction "PD5_(HS)/AIN5/LINUART_TX_2") (pintype "passive"))
    )
    (net (code "19") (name "/nRESET") (class "Default")
      (node (ref "C6") (pin "1") (pinfunction "1_1") (pintype "passive"))
      (node (ref "R5") (pin "1") (pinfunction "1_1") (pintype "passive"))
      (node (ref "R6") (pin "2") (pinfunction "2_2") (pintype "passive"))
      (node (ref "U1") (pin "4") (pinfunction "NRST_4") (pintype "passive"))
    )
    (net (code "20") (name "DGND") (class "Default")
      (node (ref "C17") (pin "1") (pinfunction "1_1") (pintype "passive"))
      (node (ref "C27") (pin "1") (pinfunction "1_1") (pintype "passive"))
      (node (ref "D7") (pin "1") (pinfunction "ANODE_1") (pintype "passive"))
      (node (ref "DGND") (pin "1") (pinfunction "1_1") (pintype "passive"))
      (node (ref "FB7") (pin "1") (pinfunction "1_1") (pintype "passive"))
      (node (ref "J3") (pin "1") (pinfunction "1_1") (pintype "passive"))
      (node (ref "L2") (pin "3") (pinfunction "3_3") (pintype "passive"))
    )
    (net (code "21") (name "GND") (class "Default")
      (node (ref "C1") (pin "2") (pinfunction "2_2") (pintype "passive"))
      (node (ref "C10") (pin "1") (pinfunction "1_1") (pintype "passive"))
      (node (ref "C11") (pin "1") (pinfunction "1_1") (pintype "passive"))
      (node (ref "C12") (pin "2") (pinfunction "2_2") (pintype "passive"))
      (node (ref "C14") (pin "1") (pinfunction "1_1") (pintype "passive"))
      (node (ref "C15") (pin "2") (pinfunction "2_2") (pintype "passive"))
      (node (ref "C18") (pin "1") (pinfunction "1_1") (pintype "passive"))
      (node (ref "C19") (pin "1") (pinfunction "1_1") (pintype "passive"))
      (node (ref "C2") (pin "1") (pinfunction "1_1") (pintype "passive"))
      (node (ref "C20") (pin "1") (pinfunction "1_1") (pintype "passive"))
      (node (ref "C21") (pin "1") (pinfunction "1_1") (pintype "passive"))
      (node (ref "C22") (pin "1") (pinfunction "1_1") (pintype "passive"))
      (node (ref "C23") (pin "1") (pinfunction "1_1") (pintype "passive"))
      (node (ref "C24") (pin "2") (pinfunction "2_2") (pintype "passive"))
      (node (ref "C25") (pin "2") (pinfunction "2_2") (pintype "passive"))
      (node (ref "C26") (pin "2") (pinfunction "2_2") (pintype "passive"))
      (node (ref "C28") (pin "1") (pinfunction "1_1") (pintype "passive"))
      (node (ref "C3") (pin "2") (pinfunction "2_2") (pintype "passive"))
      (node (ref "C4") (pin "1") (pinfunction "1_1") (pintype "passive"))
      (node (ref "C5") (pin "1") (pinfunction "1_1") (pintype "passive"))
      (node (ref "C6") (pin "2") (pinfunction "2_2") (pintype "passive"))
      (node (ref "C7") (pin "1") (pinfunction "1_1") (pintype "passive"))
      (node (ref "C8") (pin "1") (pinfunction "1_1") (pintype "passive"))
      (node (ref "C9") (pin "1") (pinfunction "1_1") (pintype "passive"))
      (node (ref "D1") (pin "1") (pinfunction "Cathode_1") (pintype "passive"))
      (node (ref "D10") (pin "1") (pinfunction "1_1") (pintype "passive"))
      (node (ref "D11") (pin "1") (pinfunction "1_1") (pintype "passive"))
      (node (ref "D4") (pin "1") (pinfunction "1_1") (pintype "passive"))
      (node (ref "D5") (pin "1") (pinfunction "1_1") (pintype "passive"))
      (node (ref "FB7") (pin "2") (pinfunction "2_2") (pintype "passive"))
      (node (ref "GND") (pin "1") (pinfunction "1_1") (pintype "passive"))
      (node (ref "J1") (pin "1") (pinfunction "1_1") (pintype "passive"))
      (node (ref "L2") (pin "4") (pinfunction "4_4") (pintype "passive"))
      (node (ref "R16") (pin "1") (pinfunction "1_1") (pintype "passive"))
      (node (ref "R19") (pin "2") (pinfunction "2_2") (pintype "passive"))
      (node (ref "R20") (pin "2") (pinfunction "2_2") (pintype "passive"))
      (node (ref "R25") (pin "2") (pinfunction "2_2") (pintype "passive"))
      (node (ref "R26") (pin "2") (pinfunction "2_2") (pintype "passive"))
      (node (ref "R30") (pin "1") (pinfunction "1_1") (pintype "passive"))
      (node (ref "U1") (pin "7") (pinfunction "VSS_7") (pintype "passive"))
      (node (ref "U2") (pin "3") (pinfunction "GND_3") (pintype "power_in"))
      (node (ref "U3") (pin "3") (pinfunction "GND_3") (pintype "power_in"))
      (node (ref "U4") (pin "3") (pinfunction "GND_3") (pintype "power_in"))
      (node (ref "U5") (pin "3") (pinfunction "GND_3") (pintype "power_in"))
      (node (ref "U6") (pin "3") (pinfunction "GND_3") (pintype "power_in"))
      (node (ref "U7") (pin "3") (pinfunction "GND_3") (pintype "power_in"))
      (node (ref "U8") (pin "1") (pinfunction "SYNC_1") (pintype "passive"))
      (node (ref "U8") (pin "2") (pinfunction "GND_2") (pintype "passive"))
      (node (ref "U8") (pin "9") (pinfunction "EPAD_9") (pintype "passive"))
    )
    (net (code "22") (name "Net-(C13-Pad2)") (class "Default")
      (node (ref "C13") (pin "2") (pinfunction "2_2") (pintype "passive"))
      (node (ref "R16") (pin "2") (pinfunction "2_2") (pintype "passive"))
    )
    (net (code "23") (name "Net-(D1-Anode)") (class "Default")
      (node (ref "C16") (pin "2") (pinfunction "2_2") (pintype "passive"))
      (node (ref "D1") (pin "2") (pinfunction "Anode_2") (pintype "passive"))
      (node (ref "L1") (pin "1") (pinfunction "1_1") (pintype "passive"))
      (node (ref "U8") (pin "6") (pinfunction "BUO_6") (pintype "passive"))
    )
    (net (code "24") (name "Net-(D2-ANODE)") (class "Default")
      (node (ref "D2") (pin "2") (pinfunction "ANODE_2") (pintype "passive"))
      (node (ref "U9") (pin "3") (pinfunction "D2_3") (pintype "passive"))
    )
    (net (code "25") (name "Net-(D2-CATHODE)") (class "Default")
      (node (ref "D2") (pin "1") (pinfunction "CATHODE_1") (pintype "passive"))
      (node (ref "R17") (pin "1") (pinfunction "1_1") (pintype "passive"))
    )
    (net (code "26") (name "Net-(D3-ANODE)") (class "Default")
      (node (ref "D3") (pin "2") (pinfunction "ANODE_2") (pintype "passive"))
      (node (ref "U10") (pin "3") (pinfunction "D2_3") (pintype "passive"))
    )
    (net (code "27") (name "Net-(D3-CATHODE)") (class "Default")
      (node (ref "D3") (pin "1") (pinfunction "CATHODE_1") (pintype "passive"))
      (node (ref "R18") (pin "1") (pinfunction "1_1") (pintype "passive"))
    )
    (net (code "28") (name "Net-(D6-Anode)") (class "Default")
      (node (ref "D6") (pin "2") (pinfunction "Anode_2") (pintype "passive"))
      (node (ref "D7") (pin "2") (pinfunction "CATHODE_2") (pintype "passive"))
      (node (ref "J3") (pin "3") (pinfunction "3_3") (pintype "passive"))
      (node (ref "VCC") (pin "1") (pinfunction "1_1") (pintype "passive"))
    )
    (net (code "29") (name "Net-(D6-Cathode)") (class "Default")
      (node (ref "C17") (pin "2") (pinfunction "2_2") (pintype "passive"))
      (node (ref "C27") (pin "2") (pinfunction "2_2") (pintype "passive"))
      (node (ref "D6") (pin "1") (pinfunction "Cathode_1") (pintype "passive"))
      (node (ref "FB2") (pin "1") (pinfunction "1_1") (pintype "passive"))
      (node (ref "L2") (pin "1") (pinfunction "1_1") (pintype "passive"))
    )
    (net (code "30") (name "Net-(D8-ANODE)") (class "Default")
      (node (ref "D8") (pin "2") (pinfunction "ANODE_2") (pintype "passive"))
      (node (ref "U9") (pin "6") (pinfunction "D1_6") (pintype "passive"))
    )
    (net (code "31") (name "Net-(D8-CATHODE)") (class "Default")
      (node (ref "D8") (pin "1") (pinfunction "CATHODE_1") (pintype "passive"))
      (node (ref "R23") (pin "1") (pinfunction "1_1") (pintype "passive"))
    )
    (net (code "32") (name "Net-(D9-ANODE)") (class "Default")
      (node (ref "D9") (pin "2") (pinfunction "ANODE_2") (pintype "passive"))
      (node (ref "U10") (pin "6") (pinfunction "D1_6") (pintype "passive"))
    )
    (net (code "33") (name "Net-(D9-CATHODE)") (class "Default")
      (node (ref "D9") (pin "1") (pinfunction "CATHODE_1") (pintype "passive"))
      (node (ref "R24") (pin "1") (pinfunction "1_1") (pintype "passive"))
    )
    (net (code "34") (name "Net-(FB3-Pad1)") (class "Default")
      (node (ref "FB3") (pin "1") (pinfunction "1_1") (pintype "passive"))
      (node (ref "R24") (pin "2") (pinfunction "2_2") (pintype "passive"))
      (node (ref "R26") (pin "1") (pinfunction "1_1") (pintype "passive"))
    )
    (net (code "35") (name "Net-(FB4-Pad1)") (class "Default")
      (node (ref "FB4") (pin "1") (pinfunction "1_1") (pintype "passive"))
      (node (ref "R18") (pin "2") (pinfunction "2_2") (pintype "passive"))
      (node (ref "R20") (pin "1") (pinfunction "1_1") (pintype "passive"))
    )
    (net (code "36") (name "Net-(FB5-Pad1)") (class "Default")
      (node (ref "FB5") (pin "1") (pinfunction "1_1") (pintype "passive"))
      (node (ref "R23") (pin "2") (pinfunction "2_2") (pintype "passive"))
      (node (ref "R25") (pin "1") (pinfunction "1_1") (pintype "passive"))
    )
    (net (code "37") (name "Net-(FB6-Pad1)") (class "Default")
      (node (ref "FB6") (pin "1") (pinfunction "1_1") (pintype "passive"))
      (node (ref "R17") (pin "2") (pinfunction "2_2") (pintype "passive"))
      (node (ref "R19") (pin "1") (pinfunction "1_1") (pintype "passive"))
    )
    (net (code "38") (name "Net-(J1-Pad5)") (class "Default")
      (node (ref "J1") (pin "5") (pinfunction "5_5") (pintype "passive"))
      (node (ref "R6") (pin "1") (pinfunction "1_1") (pintype "passive"))
    )
    (net (code "39") (name "Net-(U1-VCAP)") (class "Default")
      (node (ref "C3") (pin "1") (pinfunction "1_1") (pintype "passive"))
      (node (ref "U1") (pin "8") (pinfunction "VCAP_8") (pintype "passive"))
    )
    (net (code "40") (name "Net-(U2-VDD)") (class "Default")
      (node (ref "C4") (pin "2") (pinfunction "2_2") (pintype "passive"))
      (node (ref "R1") (pin "2") (pinfunction "2_2") (pintype "passive"))
      (node (ref "U2") (pin "1") (pinfunction "VDD_1") (pintype "power_in"))
    )
    (net (code "41") (name "Net-(U3-VDD)") (class "Default")
      (node (ref "C5") (pin "2") (pinfunction "2_2") (pintype "passive"))
      (node (ref "R2") (pin "2") (pinfunction "2_2") (pintype "passive"))
      (node (ref "U3") (pin "1") (pinfunction "VDD_1") (pintype "power_in"))
    )
    (net (code "42") (name "Net-(U4-VDD)") (class "Default")
      (node (ref "C7") (pin "2") (pinfunction "2_2") (pintype "passive"))
      (node (ref "R7") (pin "2") (pinfunction "2_2") (pintype "passive"))
      (node (ref "U4") (pin "1") (pinfunction "VDD_1") (pintype "power_in"))
    )
    (net (code "43") (name "Net-(U5-VDD)") (class "Default")
      (node (ref "C8") (pin "2") (pinfunction "2_2") (pintype "passive"))
      (node (ref "R8") (pin "2") (pinfunction "2_2") (pintype "passive"))
      (node (ref "U5") (pin "1") (pinfunction "VDD_1") (pintype "power_in"))
    )
    (net (code "44") (name "Net-(U6-VDD)") (class "Default")
      (node (ref "C9") (pin "2") (pinfunction "2_2") (pintype "passive"))
      (node (ref "R11") (pin "2") (pinfunction "2_2") (pintype "passive"))
      (node (ref "U6") (pin "1") (pinfunction "VDD_1") (pintype "power_in"))
    )
    (net (code "45") (name "Net-(U7-VDD)") (class "Default")
      (node (ref "C10") (pin "2") (pinfunction "2_2") (pintype "passive"))
      (node (ref "R12") (pin "2") (pinfunction "2_2") (pintype "passive"))
      (node (ref "U7") (pin "1") (pinfunction "VDD_1") (pintype "power_in"))
    )
    (net (code "46") (name "Net-(U8-BDS)") (class "Default")
      (node (ref "C16") (pin "1") (pinfunction "1_1") (pintype "passive"))
      (node (ref "U8") (pin "5") (pinfunction "BDS_5") (pintype "passive"))
    )
    (net (code "47") (name "Net-(U8-COMP)") (class "Default")
      (node (ref "C13") (pin "1") (pinfunction "1_1") (pintype "passive"))
      (node (ref "C24") (pin "1") (pinfunction "1_1") (pintype "passive"))
      (node (ref "U8") (pin "3") (pinfunction "COMP_3") (pintype "passive"))
    )
    (net (code "48") (name "Net-(U8-EN)") (class "Default")
      (node (ref "R15") (pin "1") (pinfunction "1_1") (pintype "passive"))
      (node (ref "U8") (pin "7") (pinfunction "EN_7") (pintype "passive"))
    )
    (net (code "49") (name "Net-(U8-FB)") (class "Default")
      (node (ref "C14") (pin "2") (pinfunction "2_2") (pintype "passive"))
      (node (ref "C19") (pin "2") (pinfunction "2_2") (pintype "passive"))
      (node (ref "FB1") (pin "1") (pinfunction "1_1") (pintype "passive"))
      (node (ref "L1") (pin "2") (pinfunction "2_2") (pintype "passive"))
      (node (ref "U8") (pin "4") (pinfunction "FB_4") (pintype "passive"))
    )
    (net (code "50") (name "VCC_5V") (class "Default")
      (node (ref "5V") (pin "1") (pinfunction "1_1") (pintype "passive"))
      (node (ref "C1") (pin "1") (pinfunction "1_1") (pintype "passive"))
      (node (ref "C15") (pin "1") (pinfunction "1_1") (pintype "passive"))
      (node (ref "C2") (pin "2") (pinfunction "2_2") (pintype "passive"))
      (node (ref "C25") (pin "1") (pinfunction "1_1") (pintype "passive"))
      (node (ref "C26") (pin "1") (pinfunction "1_1") (pintype "passive"))
      (node (ref "FB1") (pin "2") (pinfunction "2_2") (pintype "passive"))
      (node (ref "J1") (pin "2") (pinfunction "2_2") (pintype "power_in"))
      (node (ref "R1") (pin "1") (pinfunction "1_1") (pintype "passive"))
      (node (ref "R10") (pin "1") (pinfunction "1_1") (pintype "passive"))
      (node (ref "R11") (pin "1") (pinfunction "1_1") (pintype "passive"))
      (node (ref "R12") (pin "1") (pinfunction "1_1") (pintype "passive"))
      (node (ref "R13") (pin "1") (pinfunction "1_1") (pintype "passive"))
      (node (ref "R14") (pin "1") (pinfunction "1_1") (pintype "passive"))
      (node (ref "R2") (pin "1") (pinfunction "1_1") (pintype "passive"))
      (node (ref "R27") (pin "2") (pinfunction "2_2") (pintype "passive"))
      (node (ref "R28") (pin "2") (pinfunction "2_2") (pintype "passive"))
      (node (ref "R29") (pin "2") (pinfunction "2_2") (pintype "passive"))
      (node (ref "R3") (pin "1") (pinfunction "1_1") (pintype "passive"))
      (node (ref "R4") (pin "1") (pinfunction "1_1") (pintype "passive"))
      (node (ref "R5") (pin "2") (pinfunction "2_2") (pintype "passive"))
      (node (ref "R7") (pin "1") (pinfunction "1_1") (pintype "passive"))
      (node (ref "R8") (pin "1") (pinfunction "1_1") (pintype "passive"))
      (node (ref "R9") (pin "1") (pinfunction "1_1") (pintype "passive"))
      (node (ref "U1") (pin "9") (pinfunction "VDD_9") (pintype "passive"))
      (node (ref "U10") (pin "1") (pinfunction "S1_1") (pintype "passive"))
      (node (ref "U10") (pin "4") (pinfunction "S2_4") (pintype "passive"))
      (node (ref "U9") (pin "1") (pinfunction "S1_1") (pintype "passive"))
      (node (ref "U9") (pin "4") (pinfunction "S2_4") (pintype "passive"))
    )
    (net (code "51") (name "VCC_IN") (class "Default")
      (node (ref "C11") (pin "2") (pinfunction "2_2") (pintype "passive"))
      (node (ref "C12") (pin "1") (pinfunction "1_1") (pintype "passive"))
      (node (ref "C18") (pin "2") (pinfunction "2_2") (pintype "passive"))
      (node (ref "C28") (pin "2") (pinfunction "2_2") (pintype "passive"))
      (node (ref "FB2") (pin "2") (pinfunction "2_2") (pintype "passive"))
      (node (ref "L2") (pin "5") (pinfunction "5_5") (pintype "passive"))
      (node (ref "R15") (pin "2") (pinfunction "2_2") (pintype "passive"))
      (node (ref "U8") (pin "8") (pinfunction "VS_8") (pintype "passive"))
    )
    (net (code "52") (name "unconnected-(FID1-Pad0)") (class "Default")
      (node (ref "FID1") (pin "0") (pinfunction "0_0") (pintype "passive+no_connect"))
    )
    (net (code "53") (name "unconnected-(FID2-Pad0)") (class "Default")
      (node (ref "FID2") (pin "0") (pinfunction "0_0") (pintype "passive+no_connect"))
    )
    (net (code "54") (name "unconnected-(FID3-Pad0)") (class "Default")
      (node (ref "FID3") (pin "0") (pinfunction "0_0") (pintype "passive+no_connect"))
    )
    (net (code "55") (name "unconnected-(FID4-Pad0)") (class "Default")
      (node (ref "FID4") (pin "0") (pinfunction "0_0") (pintype "passive+no_connect"))
    )
    (net (code "56") (name "unconnected-(U1-PA1{slash}OSCIN-Pad5)") (class "Default")
      (node (ref "U1") (pin "5") (pinfunction "PA1/OSCIN_5") (pintype "passive+no_connect"))
    )
    (net (code "57") (name "unconnected-(U1-PA2{slash}OSCOUT-Pad6)") (class "Default")
      (node (ref "U1") (pin "6") (pinfunction "PA2/OSCOUT_6") (pintype "passive+no_connect"))
    )
  )
)
